# mcp23007_uln2803a_fabricated.net
KiCad netlist of a schematic drawn in EAGLE
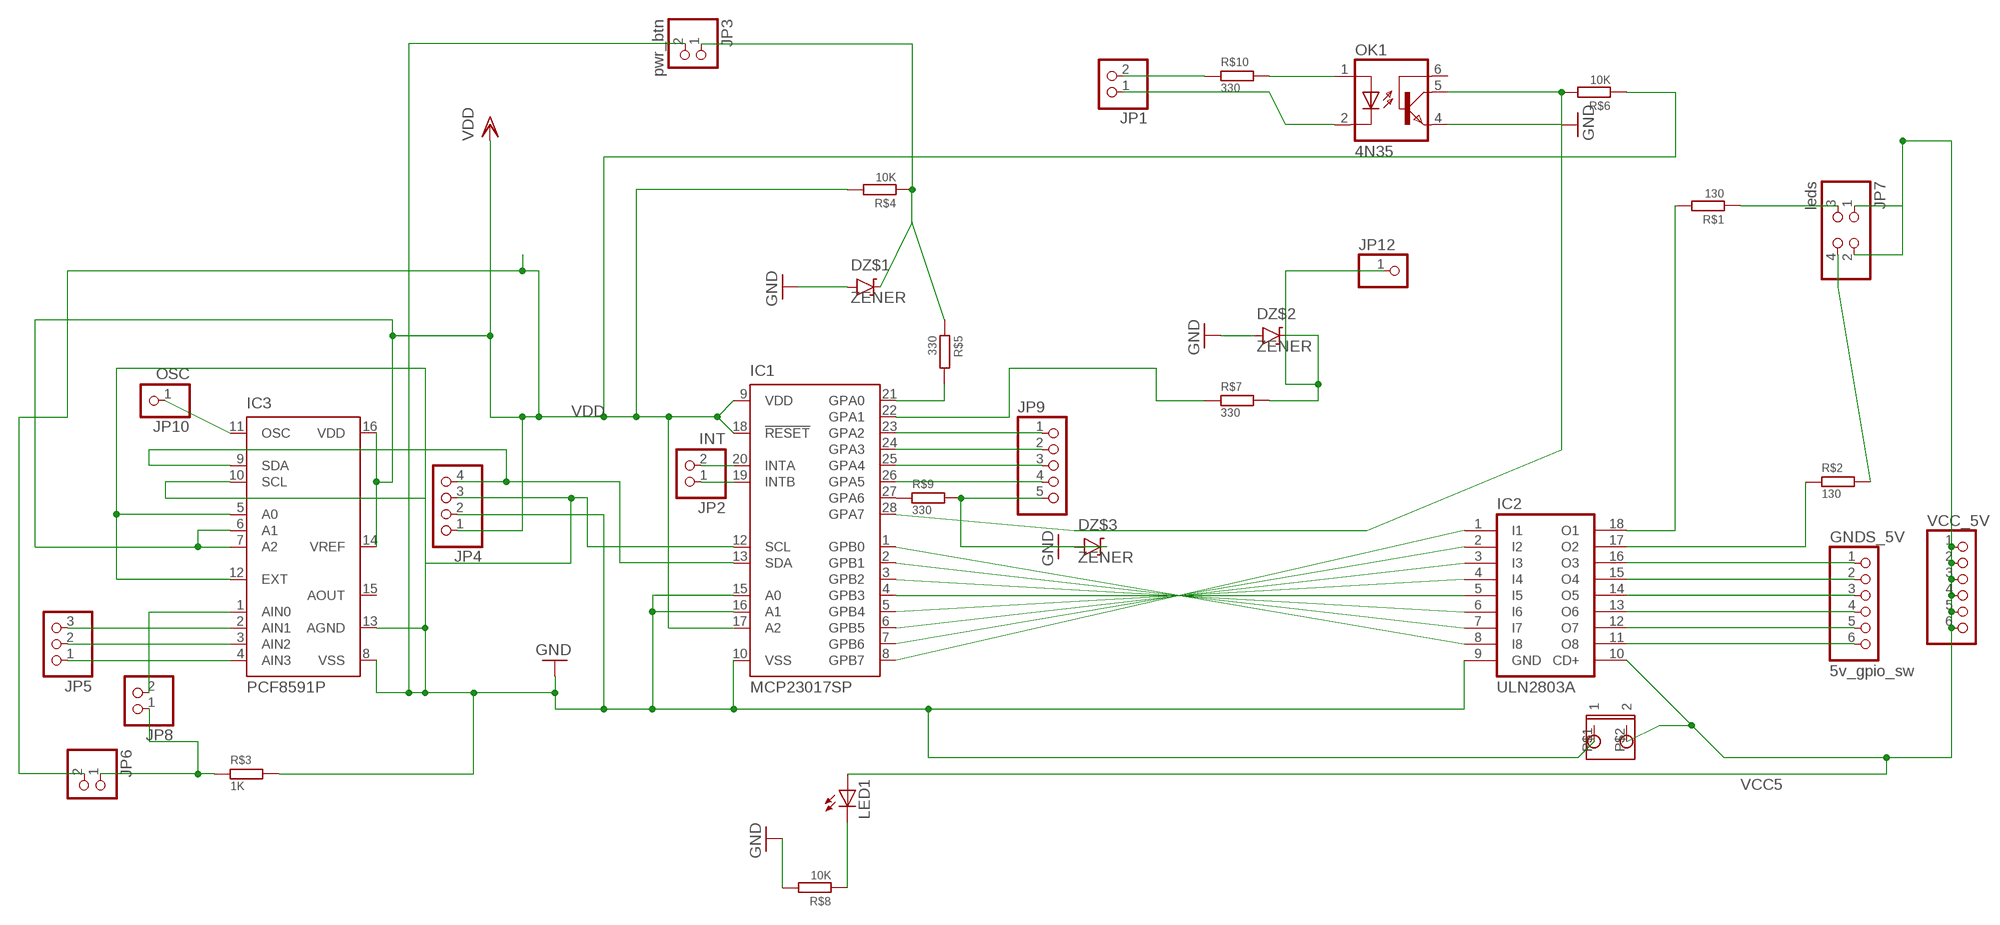
[diagram p0: schematic, sheet 1]

(export (version "E")
  (design (tool "Eeschema 10.0.6"))
  (components
    (comp (ref "DZ$1")
      (value "ZENER")
      (footprint "eagle-import:ZENER")
      (libsource (lib "eagle-import") (part "ZENER"))
    )
    (comp (ref "DZ$2")
      (value "ZENER")
      (footprint "eagle-import:ZENER")
      (libsource (lib "eagle-import") (part "ZENER"))
    )
    (comp (ref "DZ$3")
      (value "ZENER")
      (footprint "eagle-import:ZENER")
      (libsource (lib "eagle-import") (part "ZENER"))
    )
    (comp (ref "GNDS_5V")
      (value "5v_gpio_sw")
      (footprint "eagle-import:1X06")
      (libsource (lib "eagle-import") (part "PINHD-1X6"))
    )
    (comp (ref "IC1")
      (value "MCP23017SP")
      (footprint "eagle-import:DIL28-3")
      (fields (field (name "MF") "MICROCHIP") (field (name "MPN") "MCP23017-E/SP"))
      (libsource (lib "eagle-import") (part "MCP23017SP"))
    )
    (comp (ref "IC2")
      (value "ULN2803A")
      (footprint "eagle-import:DIL18")
      (libsource (lib "eagle-import") (part "ULN2803A"))
    )
    (comp (ref "IC3")
      (value "PCF8591P")
      (footprint "eagle-import:DIL16")
      (fields (field (name "MF") "FARNELL"))
      (libsource (lib "eagle-import") (part "PCF8591P"))
    )
    (comp (ref "JP1")
      (value "PINHD-1X2")
      (footprint "eagle-import:1X02")
      (libsource (lib "eagle-import") (part "PINHD-1X2"))
    )
    (comp (ref "JP2")
      (value "INT")
      (footprint "eagle-import:1X02")
      (libsource (lib "eagle-import") (part "PINHD-1X2"))
    )
    (comp (ref "JP3")
      (value "pwr_btn")
      (footprint "eagle-import:1X02")
      (libsource (lib "eagle-import") (part "PINHD-1X2"))
    )
    (comp (ref "JP4")
      (value "PINHD-1X4")
      (footprint "eagle-import:1X04")
      (libsource (lib "eagle-import") (part "PINHD-1X4"))
    )
    (comp (ref "JP5")
      (value "PINHD-1X3")
      (footprint "eagle-import:1X03")
      (libsource (lib "eagle-import") (part "PINHD-1X3"))
    )
    (comp (ref "JP6")
      (value "PINHD-1X2")
      (footprint "eagle-import:1X02")
      (libsource (lib "eagle-import") (part "PINHD-1X2"))
    )
    (comp (ref "JP7")
      (value "leds")
      (footprint "eagle-import:2X02")
      (libsource (lib "eagle-import") (part "PINHD-2X2"))
    )
    (comp (ref "JP8")
      (value "PINHD-1X2")
      (footprint "eagle-import:1X02")
      (libsource (lib "eagle-import") (part "PINHD-1X2"))
    )
    (comp (ref "JP9")
      (value "PINHD-1X5")
      (footprint "eagle-import:1X05")
      (libsource (lib "eagle-import") (part "PINHD-1X5"))
    )
    (comp (ref "JP10")
      (value "OSC")
      (footprint "eagle-import:1X01")
      (libsource (lib "eagle-import") (part "pinhead_PINHD-1X1"))
    )
    (comp (ref "JP12")
      (value "PINHD-1X1")
      (footprint "eagle-import:1X01")
      (libsource (lib "eagle-import") (part "PINHD-1X1"))
    )
    (comp (ref "LED1")
      (value "LED3MM")
      (footprint "eagle-import:LED3MM")
      (libsource (lib "eagle-import") (part "LED3MM"))
    )
    (comp (ref "OK1")
      (value "4N35")
      (footprint "eagle-import:DIL06")
      (fields (field (name "MF") "FAIRCHILD SEMICONDUCTOR"))
      (libsource (lib "eagle-import") (part "4N35"))
    )
    (comp (ref "R$1")
      (value "130")
      (footprint "eagle-import:RESISTOR_1_4")
      (libsource (lib "eagle-import") (part "RESISTOR"))
    )
    (comp (ref "R$2")
      (value "130")
      (footprint "eagle-import:RESISTOR_1_4")
      (libsource (lib "eagle-import") (part "RESISTOR"))
    )
    (comp (ref "R$3")
      (value "1K")
      (footprint "eagle-import:RESISTOR_1_4")
      (libsource (lib "eagle-import") (part "RESISTOR"))
    )
    (comp (ref "R$4")
      (value "10K")
      (footprint "eagle-import:RESISTOR_1_4")
      (libsource (lib "eagle-import") (part "RESISTOR"))
    )
    (comp (ref "R$5")
      (value "330")
      (footprint "eagle-import:RESISTOR_1_4")
      (libsource (lib "eagle-import") (part "RESISTOR"))
    )
    (comp (ref "R$6")
      (value "10K")
      (footprint "eagle-import:RESISTOR_1_4")
      (libsource (lib "eagle-import") (part "RESISTOR"))
    )
    (comp (ref "R$7")
      (value "330")
      (footprint "eagle-import:RESISTOR_1_4")
      (libsource (lib "eagle-import") (part "RESISTOR"))
    )
    (comp (ref "R$8")
      (value "10K")
      (footprint "eagle-import:RESISTOR_1_4")
      (libsource (lib "eagle-import") (part "RESISTOR"))
    )
    (comp (ref "R$9")
      (value "330")
      (footprint "eagle-import:RESISTOR_1_4")
      (libsource (lib "eagle-import") (part "RESISTOR"))
    )
    (comp (ref "R$10")
      (value "330")
      (footprint "eagle-import:RESISTOR_1_4")
      (libsource (lib "eagle-import") (part "RESISTOR"))
    )
    (comp (ref "U$1")
      (value "5.5MM_PIN")
      (footprint "eagle-import:5.5MM_PIN")
      (libsource (lib "eagle-import") (part "5.5MM_PIN"))
    )
    (comp (ref "VCC_5V")
      (value "PINHD-1X6")
      (footprint "eagle-import:1X06")
      (libsource (lib "eagle-import") (part "PINHD-1X6"))
    )
  )
  (nets
    (net (code "1") (name "/VCC5") (class "Default")
      (node (ref "IC2") (pin "10") (pinfunction "CD+_10") (pintype "passive"))
      (node (ref "JP7") (pin "1") (pinfunction "1_1") (pintype "passive"))
      (node (ref "JP7") (pin "2") (pinfunction "2_2") (pintype "passive"))
      (node (ref "LED1") (pin "A") (pinfunction "A_A") (pintype "passive"))
      (node (ref "U$1") (pin "P$2") (pinfunction "2_P$2") (pintype "bidirectional"))
      (node (ref "VCC_5V") (pin "1") (pinfunction "1_1") (pintype "passive"))
      (node (ref "VCC_5V") (pin "2") (pinfunction "2_2") (pintype "passive"))
      (node (ref "VCC_5V") (pin "3") (pinfunction "3_3") (pintype "passive"))
      (node (ref "VCC_5V") (pin "4") (pinfunction "4_4") (pintype "passive"))
      (node (ref "VCC_5V") (pin "5") (pinfunction "5_5") (pintype "passive"))
      (node (ref "VCC_5V") (pin "6") (pinfunction "6_6") (pintype "passive"))
    )
    (net (code "2") (name "GND") (class "Default")
      (node (ref "DZ$1") (pin "P$1") (pinfunction "P$2_P$1") (pintype "passive"))
      (node (ref "DZ$2") (pin "P$1") (pinfunction "P$2_P$1") (pintype "passive"))
      (node (ref "DZ$3") (pin "P$1") (pinfunction "P$2_P$1") (pintype "passive"))
      (node (ref "IC1") (pin "10") (pinfunction "VSS_10") (pintype "power_in"))
      (node (ref "IC1") (pin "15") (pinfunction "A0_15") (pintype "input"))
      (node (ref "IC1") (pin "16") (pinfunction "A1_16") (pintype "input"))
      (node (ref "IC2") (pin "9") (pinfunction "GND_9") (pintype "power_in"))
      (node (ref "IC3") (pin "12") (pinfunction "EXT_12") (pintype "input"))
      (node (ref "IC3") (pin "13") (pinfunction "AGND_13") (pintype "power_in"))
      (node (ref "IC3") (pin "5") (pinfunction "A0_5") (pintype "input"))
      (node (ref "IC3") (pin "8") (pinfunction "VSS_8") (pintype "power_in"))
      (node (ref "JP3") (pin "2") (pinfunction "2_2") (pintype "passive"))
      (node (ref "JP4") (pin "2") (pinfunction "2_2") (pintype "passive"))
      (node (ref "OK1") (pin "4") (pinfunction "EMI_4") (pintype "passive"))
      (node (ref "R$3") (pin "P$1") (pinfunction "P$1_P$1") (pintype "passive"))
      (node (ref "R$8") (pin "P$1") (pinfunction "P$1_P$1") (pintype "passive"))
      (node (ref "U$1") (pin "P$1") (pinfunction "1_P$1") (pintype "bidirectional"))
    )
    (net (code "3") (name "Net-(DZ$1-P$3)") (class "Default")
      (node (ref "DZ$1") (pin "P$2") (pinfunction "P$3_P$2") (pintype "passive"))
      (node (ref "JP3") (pin "1") (pinfunction "1_1") (pintype "passive"))
      (node (ref "R$4") (pin "P$2") (pinfunction "P$2_P$2") (pintype "passive"))
      (node (ref "R$5") (pin "P$2") (pinfunction "P$2_P$2") (pintype "passive"))
    )
    (net (code "4") (name "Net-(DZ$2-P$3)") (class "Default")
      (node (ref "DZ$2") (pin "P$2") (pinfunction "P$3_P$2") (pintype "passive"))
      (node (ref "JP12") (pin "1") (pinfunction "1_1") (pintype "passive"))
      (node (ref "R$7") (pin "P$1") (pinfunction "P$1_P$1") (pintype "passive"))
    )
    (net (code "5") (name "Net-(DZ$3-P$3)") (class "Default")
      (node (ref "DZ$3") (pin "P$2") (pinfunction "P$3_P$2") (pintype "passive"))
      (node (ref "JP9") (pin "5") (pinfunction "5_5") (pintype "passive"))
      (node (ref "R$9") (pin "P$1") (pinfunction "P$1_P$1") (pintype "passive"))
    )
    (net (code "6") (name "Net-(IC1-GPA0)") (class "Default")
      (node (ref "IC1") (pin "21") (pinfunction "GPA0_21") (pintype "bidirectional"))
      (node (ref "R$5") (pin "P$1") (pinfunction "P$1_P$1") (pintype "passive"))
    )
    (net (code "7") (name "Net-(IC1-GPA1)") (class "Default")
      (node (ref "IC1") (pin "22") (pinfunction "GPA1_22") (pintype "bidirectional"))
      (node (ref "R$7") (pin "P$2") (pinfunction "P$2_P$2") (pintype "passive"))
    )
    (net (code "8") (name "Net-(IC1-GPA2)") (class "Default")
      (node (ref "IC1") (pin "23") (pinfunction "GPA2_23") (pintype "bidirectional"))
      (node (ref "JP9") (pin "1") (pinfunction "1_1") (pintype "passive"))
    )
    (net (code "9") (name "Net-(IC1-GPA3)") (class "Default")
      (node (ref "IC1") (pin "24") (pinfunction "GPA3_24") (pintype "bidirectional"))
      (node (ref "JP9") (pin "2") (pinfunction "2_2") (pintype "passive"))
    )
    (net (code "10") (name "Net-(IC1-GPA4)") (class "Default")
      (node (ref "IC1") (pin "25") (pinfunction "GPA4_25") (pintype "bidirectional"))
      (node (ref "JP9") (pin "3") (pinfunction "3_3") (pintype "passive"))
    )
    (net (code "11") (name "Net-(IC1-GPA5)") (class "Default")
      (node (ref "IC1") (pin "26") (pinfunction "GPA5_26") (pintype "bidirectional"))
      (node (ref "JP9") (pin "4") (pinfunction "4_4") (pintype "passive"))
    )
    (net (code "12") (name "Net-(IC1-GPA6)") (class "Default")
      (node (ref "IC1") (pin "27") (pinfunction "GPA6_27") (pintype "bidirectional"))
      (node (ref "R$9") (pin "P$2") (pinfunction "P$2_P$2") (pintype "passive"))
    )
    (net (code "13") (name "Net-(IC1-GPA7)") (class "Default")
      (node (ref "IC1") (pin "28") (pinfunction "GPA7_28") (pintype "bidirectional"))
      (node (ref "OK1") (pin "5") (pinfunction "COL_5") (pintype "passive"))
      (node (ref "R$6") (pin "P$1") (pinfunction "P$1_P$1") (pintype "passive"))
    )
    (net (code "14") (name "Net-(IC1-GPB0)") (class "Default")
      (node (ref "IC1") (pin "1") (pinfunction "GPB0_1") (pintype "bidirectional"))
      (node (ref "IC2") (pin "8") (pinfunction "I8_8") (pintype "input"))
    )
    (net (code "15") (name "Net-(IC1-GPB1)") (class "Default")
      (node (ref "IC1") (pin "2") (pinfunction "GPB1_2") (pintype "bidirectional"))
      (node (ref "IC2") (pin "7") (pinfunction "I7_7") (pintype "input"))
    )
    (net (code "16") (name "Net-(IC1-GPB2)") (class "Default")
      (node (ref "IC1") (pin "3") (pinfunction "GPB2_3") (pintype "bidirectional"))
      (node (ref "IC2") (pin "6") (pinfunction "I6_6") (pintype "input"))
    )
    (net (code "17") (name "Net-(IC1-GPB3)") (class "Default")
      (node (ref "IC1") (pin "4") (pinfunction "GPB3_4") (pintype "bidirectional"))
      (node (ref "IC2") (pin "5") (pinfunction "I5_5") (pintype "input"))
    )
    (net (code "18") (name "Net-(IC1-GPB4)") (class "Default")
      (node (ref "IC1") (pin "5") (pinfunction "GPB4_5") (pintype "bidirectional"))
      (node (ref "IC2") (pin "4") (pinfunction "I4_4") (pintype "input"))
    )
    (net (code "19") (name "Net-(IC1-GPB5)") (class "Default")
      (node (ref "IC1") (pin "6") (pinfunction "GPB5_6") (pintype "bidirectional"))
      (node (ref "IC2") (pin "3") (pinfunction "I3_3") (pintype "input"))
    )
    (net (code "20") (name "Net-(IC1-GPB6)") (class "Default")
      (node (ref "IC1") (pin "7") (pinfunction "GPB6_7") (pintype "bidirectional"))
      (node (ref "IC2") (pin "2") (pinfunction "I2_2") (pintype "input"))
    )
    (net (code "21") (name "Net-(IC1-GPB7)") (class "Default")
      (node (ref "IC1") (pin "8") (pinfunction "GPB7_8") (pintype "bidirectional"))
      (node (ref "IC2") (pin "1") (pinfunction "I1_1") (pintype "input"))
    )
    (net (code "22") (name "Net-(IC1-INTA)") (class "Default")
      (node (ref "IC1") (pin "20") (pinfunction "INTA_20") (pintype "output"))
      (node (ref "JP2") (pin "2") (pinfunction "2_2") (pintype "passive"))
    )
    (net (code "23") (name "Net-(IC1-INTB)") (class "Default")
      (node (ref "IC1") (pin "19") (pinfunction "INTB_19") (pintype "output"))
      (node (ref "JP2") (pin "1") (pinfunction "1_1") (pintype "passive"))
    )
    (net (code "24") (name "Net-(IC1-SCL)") (class "Default")
      (node (ref "IC1") (pin "12") (pinfunction "SCL_12") (pintype "input"))
      (node (ref "IC3") (pin "10") (pinfunction "SCL_10") (pintype "input"))
      (node (ref "JP4") (pin "3") (pinfunction "3_3") (pintype "passive"))
    )
    (net (code "25") (name "Net-(IC1-SDA)") (class "Default")
      (node (ref "IC1") (pin "13") (pinfunction "SDA_13") (pintype "bidirectional"))
      (node (ref "IC3") (pin "9") (pinfunction "SDA_9") (pintype "bidirectional"))
      (node (ref "JP4") (pin "4") (pinfunction "4_4") (pintype "passive"))
    )
    (net (code "26") (name "Net-(IC2-O1)") (class "Default")
      (node (ref "IC2") (pin "18") (pinfunction "O1_18") (pintype "open_collector"))
      (node (ref "R$1") (pin "P$1") (pinfunction "P$1_P$1") (pintype "passive"))
    )
    (net (code "27") (name "Net-(IC2-O2)") (class "Default")
      (node (ref "IC2") (pin "17") (pinfunction "O2_17") (pintype "open_collector"))
      (node (ref "R$2") (pin "P$2") (pinfunction "P$2_P$2") (pintype "passive"))
    )
    (net (code "28") (name "Net-(IC2-O3)") (class "Default")
      (node (ref "GNDS_5V") (pin "1") (pinfunction "1_1") (pintype "passive"))
      (node (ref "IC2") (pin "16") (pinfunction "O3_16") (pintype "open_collector"))
    )
    (net (code "29") (name "Net-(IC2-O4)") (class "Default")
      (node (ref "GNDS_5V") (pin "2") (pinfunction "2_2") (pintype "passive"))
      (node (ref "IC2") (pin "15") (pinfunction "O4_15") (pintype "open_collector"))
    )
    (net (code "30") (name "Net-(IC2-O5)") (class "Default")
      (node (ref "GNDS_5V") (pin "3") (pinfunction "3_3") (pintype "passive"))
      (node (ref "IC2") (pin "14") (pinfunction "O5_14") (pintype "open_collector"))
    )
    (net (code "31") (name "Net-(IC2-O6)") (class "Default")
      (node (ref "GNDS_5V") (pin "4") (pinfunction "4_4") (pintype "passive"))
      (node (ref "IC2") (pin "13") (pinfunction "O6_13") (pintype "open_collector"))
    )
    (net (code "32") (name "Net-(IC2-O7)") (class "Default")
      (node (ref "GNDS_5V") (pin "5") (pinfunction "5_5") (pintype "passive"))
      (node (ref "IC2") (pin "12") (pinfunction "O7_12") (pintype "open_collector"))
    )
    (net (code "33") (name "Net-(IC2-O8)") (class "Default")
      (node (ref "GNDS_5V") (pin "6") (pinfunction "6_6") (pintype "passive"))
      (node (ref "IC2") (pin "11") (pinfunction "O8_11") (pintype "open_collector"))
    )
    (net (code "34") (name "Net-(IC3-AIN0)") (class "Default")
      (node (ref "IC3") (pin "1") (pinfunction "AIN0_1") (pintype "input"))
      (node (ref "JP8") (pin "2") (pinfunction "2_2") (pintype "passive"))
    )
    (net (code "35") (name "Net-(IC3-AIN1)") (class "Default")
      (node (ref "IC3") (pin "2") (pinfunction "AIN1_2") (pintype "input"))
      (node (ref "JP5") (pin "3") (pinfunction "3_3") (pintype "passive"))
    )
    (net (code "36") (name "Net-(IC3-AIN2)") (class "Default")
      (node (ref "IC3") (pin "3") (pinfunction "AIN2_3") (pintype "input"))
      (node (ref "JP5") (pin "2") (pinfunction "2_2") (pintype "passive"))
    )
    (net (code "37") (name "Net-(IC3-AIN3)") (class "Default")
      (node (ref "IC3") (pin "4") (pinfunction "AIN3_4") (pintype "input"))
      (node (ref "JP5") (pin "1") (pinfunction "1_1") (pintype "passive"))
    )
    (net (code "38") (name "Net-(IC3-OSC)") (class "Default")
      (node (ref "IC3") (pin "11") (pinfunction "OSC_11") (pintype "input"))
      (node (ref "JP10") (pin "1") (pinfunction "1_1") (pintype "passive"))
    )
    (net (code "39") (name "Net-(JP1-Pad2)") (class "Default")
      (node (ref "JP1") (pin "2") (pinfunction "2_2") (pintype "passive"))
      (node (ref "R$10") (pin "P$2") (pinfunction "P$2_P$2") (pintype "passive"))
    )
    (net (code "40") (name "Net-(JP6-Pad1)") (class "Default")
      (node (ref "JP6") (pin "1") (pinfunction "1_1") (pintype "passive"))
      (node (ref "JP8") (pin "1") (pinfunction "1_1") (pintype "passive"))
      (node (ref "R$3") (pin "P$2") (pinfunction "P$2_P$2") (pintype "passive"))
    )
    (net (code "41") (name "Net-(JP7-Pad3)") (class "Default")
      (node (ref "JP7") (pin "3") (pinfunction "3_3") (pintype "passive"))
      (node (ref "R$1") (pin "P$2") (pinfunction "P$2_P$2") (pintype "passive"))
    )
    (net (code "42") (name "Net-(JP7-Pad4)") (class "Default")
      (node (ref "JP7") (pin "4") (pinfunction "4_4") (pintype "passive"))
      (node (ref "R$2") (pin "P$1") (pinfunction "P$1_P$1") (pintype "passive"))
    )
    (net (code "43") (name "Net-(LED1-C)") (class "Default")
      (node (ref "LED1") (pin "K") (pinfunction "C_K") (pintype "passive"))
      (node (ref "R$8") (pin "P$2") (pinfunction "P$2_P$2") (pintype "passive"))
    )
    (net (code "44") (name "Net-(OK1-A)") (class "Default")
      (node (ref "OK1") (pin "1") (pinfunction "A_1") (pintype "passive"))
      (node (ref "R$10") (pin "P$1") (pinfunction "P$1_P$1") (pintype "passive"))
    )
    (net (code "45") (name "Net-(OK1-C)") (class "Default")
      (node (ref "JP1") (pin "1") (pinfunction "1_1") (pintype "passive"))
      (node (ref "OK1") (pin "2") (pinfunction "C_2") (pintype "passive"))
    )
    (net (code "46") (name "VDD") (class "Default")
      (node (ref "IC1") (pin "17") (pinfunction "A2_17") (pintype "input"))
      (node (ref "IC1") (pin "18") (pinfunction "~{RESET}_18") (pintype "input"))
      (node (ref "IC1") (pin "9") (pinfunction "VDD_9") (pintype "power_in"))
      (node (ref "IC3") (pin "14") (pinfunction "VREF_14") (pintype "input"))
      (node (ref "IC3") (pin "16") (pinfunction "VDD_16") (pintype "power_in"))
      (node (ref "IC3") (pin "6") (pinfunction "A1_6") (pintype "input"))
      (node (ref "IC3") (pin "7") (pinfunction "A2_7") (pintype "input"))
      (node (ref "JP4") (pin "1") (pinfunction "1_1") (pintype "passive"))
      (node (ref "JP6") (pin "2") (pinfunction "2_2") (pintype "passive"))
      (node (ref "R$4") (pin "P$1") (pinfunction "P$1_P$1") (pintype "passive"))
      (node (ref "R$6") (pin "P$2") (pinfunction "P$2_P$2") (pintype "passive"))
    )
    (net (code "47") (name "unconnected-(IC3-AOUT-Pad15)") (class "Default")
      (node (ref "IC3") (pin "15") (pinfunction "AOUT_15") (pintype "output"))
    )
    (net (code "48") (name "unconnected-(OK1-BAS-Pad6)") (class "Default")
      (node (ref "OK1") (pin "6") (pinfunction "BAS_6") (pintype "passive"))
    )
  )
)
